# PowerConverters.net
KiCad netlist of a schematic drawn in Altium Designer
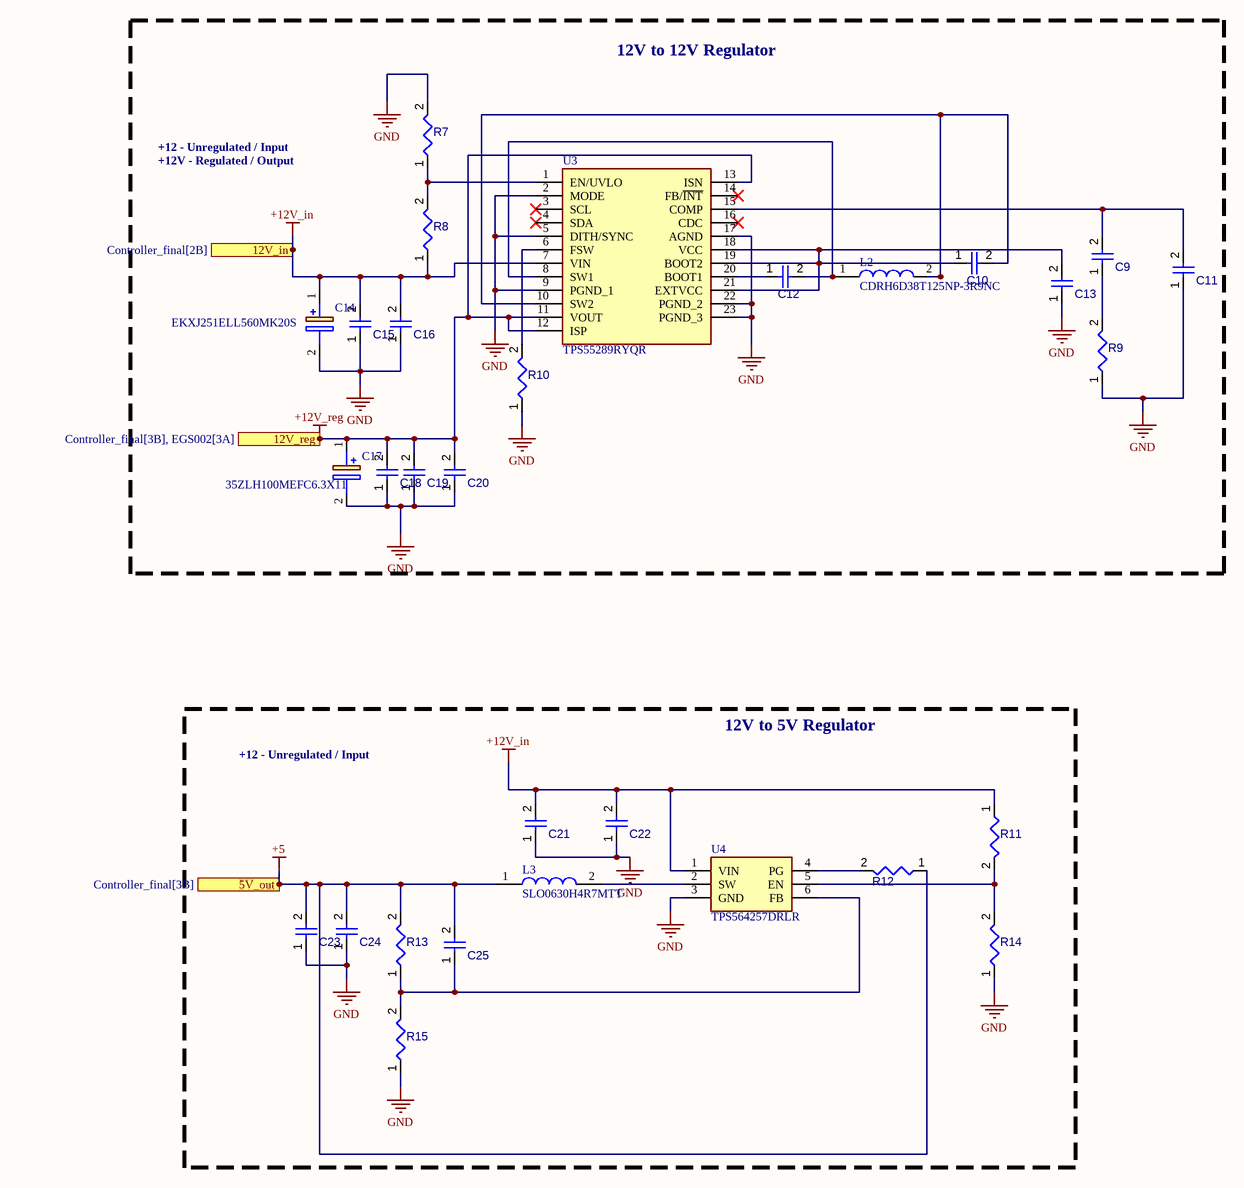
[diagram p0: PowerConverters.SchDoc]

(export (version "E")
  (design (tool "Eeschema 10.0.6"))
  (components
    (comp (ref "C9")
      (value "Capacitor 1nF +/-20% 50V 0402")
      (footprint "CAPC0402(1005)33_L")
      (description "Chip Capacitor, 1nF +/-20%, 50V, 0402, Thickness 0.33 mm")
      (fields (field (name "TOLERANCE") "10%"))
      (libsource (lib "Rahulb 23") (part "CAP-NP-2"))
    )
    (comp (ref "C10")
      (value "Capacitor 100 nF +/-10% 50 V 0603")
      (footprint "CAPC1608X90X40NL10T20")
      (description "Chip Capacitor, 100 nF, +/- 10%, 50 V, 0603 (1608 Metric)")
      (fields (field (name "TOLERANCE") "10%"))
      (libsource (lib "Rahulb 23") (part "CAP-NP-2"))
    )
    (comp (ref "C11")
      (value "Capacitor 1 uF +/- 10% 25 V 0805")
      (footprint "CAPC2013X145X50ML20T25")
      (description "Chip Capacitor, 5.1pF, +/-10%, 250 V, 0805 (2012 Metric)")
      (fields (field (name "TOLERANCE") "10%"))
      (libsource (lib "Rahulb 23") (part "CAP-NP-2"))
    )
    (comp (ref "C12")
      (value "Capacitor 100 nF +/-10% 50 V 0603")
      (footprint "CAPC1608X90X40NL10T20")
      (description "Chip Capacitor, 100 nF, +/- 10%, 50 V, 0603 (1608 Metric)")
      (fields (field (name "TOLERANCE") "10%"))
      (libsource (lib "Rahulb 23") (part "CAP-NP-2"))
    )
    (comp (ref "C13")
      (value "Capacitor 4.7µF +/-40% 25V 0805")
      (footprint "CAPC0805(2012)145_L")
      (description "Chip Capacitor, 4.7µF +/-40%, 25V, 0805, Thickness 1.45 mm")
      (fields (field (name "TOLERANCE") "20%"))
      (libsource (lib "Rahulb 23") (part "CAP-NP-2"))
    )
    (comp (ref "C14")
      (value "EKXJ251ELL560MK20S")
      (footprint "CAPPRD500W60D1275H2000 - duplicate")
      (description "56uF 250V Aluminum Electrolytic Capacitors Through Hole,D12.5xL20mm 10000hrs@105℃")
      (fields
        (field (name "MANUFACTURER_PART_NUMBER") "UPW0J222MHD")
        (field (name "MOUSER PART NUMBER") "647-UPW0J222MHD")
      )
      (libsource (lib "myComponents") (part "UPW0J222MHD"))
    )
    (comp (ref "C15")
      (value "Capacitor 22µF +/-40% 16V 0805")
      (footprint "CAPC0805(2012)145_L")
      (description "Chip Capacitor, 22µF +/-20%, 25V, 0805, Thickness 1.45 mm X5R")
      (fields (field (name "TOLERANCE") "5%"))
      (libsource (lib "Rahulb 23") (part "CAP-NP-2"))
    )
    (comp (ref "C16")
      (value "Capacitor 1µF +/-40% 50V 0603")
      (footprint "CAPC0603(1608)100_L")
      (description "Chip Capacitor, 1µF +/-40%, 50V, 0603, Thickness 1 mm")
      (fields (field (name "TOLERANCE") "10%"))
      (libsource (lib "Rahulb 23") (part "CAP-NP-2"))
    )
    (comp (ref "C17")
      (value "35ZLH100MEFC6.3X11")
      (footprint "CAPPRD250W50D680H1250")
      (description "100uF 35V Aluminum Electrolytic Capacitors Through Hole,D6.3xL11mm 6000hrs@105℃")
      (fields
        (field (name "MANUFACTURER_PART_NUMBER") "MAL203856101E3")
        (field (name "MOUSER PART NUMBER") "594-MAL203856101E3")
      )
      (libsource (lib "myComponents") (part "MAL203856101E3"))
    )
    (comp (ref "C18")
      (value "Capacitor 22µF +/-40% 16V 0805")
      (footprint "CAPC0805(2012)145_L")
      (description "Chip Capacitor, 22µF +/-20%, 25V, 0805, Thickness 1.45 mm X5R")
      (fields (field (name "TOLERANCE") "5%"))
      (libsource (lib "Rahulb 23") (part "CAP-NP-2"))
    )
    (comp (ref "C19")
      (value "Capacitor 22µF +/-40% 16V 0805")
      (footprint "CAPC0805(2012)145_L")
      (description "Chip Capacitor, 22µF +/-20%, 25V, 0805, Thickness 1.45 mm X5R")
      (fields (field (name "TOLERANCE") "5%"))
      (libsource (lib "Rahulb 23") (part "CAP-NP-2"))
    )
    (comp (ref "C20")
      (value "Capacitor 1µF +/-40% 50V 0603")
      (footprint "CAPC0603(1608)100_L")
      (description "Chip Capacitor, 1µF +/-40%, 50V, 0603, Thickness 1 mm")
      (fields (field (name "TOLERANCE") "10%"))
      (libsource (lib "Rahulb 23") (part "CAP-NP-2"))
    )
    (comp (ref "C21")
      (value "Capacitor 22µF +/-40% 16V 0805")
      (footprint "CAPC0805(2012)145_L")
      (description "Chip Capacitor, 22µF +/-20%, 25V, 0805, Thickness 1.45 mm X5R")
      (fields (field (name "TOLERANCE") "5%"))
      (libsource (lib "Rahulb 23") (part "CAP-NP-2"))
    )
    (comp (ref "C22")
      (value "Capacitor 100 nF +/-10% 50 V 0603")
      (footprint "CAPC1608X90X40NL10T20")
      (description "Chip Capacitor, 100 nF, +/- 10%, 50 V, 0603 (1608 Metric)")
      (fields (field (name "TOLERANCE") "10%"))
      (libsource (lib "Rahulb 23") (part "CAP-NP-2"))
    )
    (comp (ref "C23")
      (value "Capacitor 22µF +/-40% 16V 0805")
      (footprint "CAPC0805(2012)145_L")
      (description "Chip Capacitor, 22µF +/-20%, 25V, 0805, Thickness 1.45 mm X5R")
      (fields (field (name "TOLERANCE") "5%"))
      (libsource (lib "Rahulb 23") (part "CAP-NP-2"))
    )
    (comp (ref "C24")
      (value "Capacitor 100 nF +/-10% 50 V 0603")
      (footprint "CAPC1608X90X40NL10T20")
      (description "Chip Capacitor, 100 nF, +/- 10%, 50 V, 0603 (1608 Metric)")
      (fields (field (name "TOLERANCE") "10%"))
      (libsource (lib "Rahulb 23") (part "CAP-NP-2"))
    )
    (comp (ref "C25")
      (value "Capacitor 10 pF +/- 0.25 pF 50 V 0603")
      (footprint "CAPC1608X87X35NL15T15")
      (description "Chip Capacitor, 10 pF, +/- 0.25 pF, 50 V, 0603 (1608 Metric)")
      (fields (field (name "TOLERANCE") "0.25%"))
      (libsource (lib "Rahulb 23") (part "CAP-NP-2"))
    )
    (comp (ref "L2")
      (value "CDRH6D38T125NP-3R9NC")
      (footprint "SamacSys:CDRH6D18HPNP101PC")
      (description "Inductor 3.9uH ,19.6mOhm, SMD, 6.7mm X 6.7mm")
      (fields (field (name "MANUFACTURER_PART_NUMBER") "CDRH6D18HPNP-101PC"))
      (libsource (lib "*") (part "CDRH6D18HPNP-101PC"))
    )
    (comp (ref "L3")
      (value "SLO0630H4R7MTT")
      (footprint "INDPM7166X300N")
      (description "5.5A 4.7uH ±20% 9A 38mΩ Magnetic Shielded Inductor SMD,7.1x6.6mm Fixed Inductors RoHS")
      (fields
        (field (name "MANUFACTURER_PART_NUMBER") "SRP6530A-R47M")
        (field (name "MOUSER PART NUMBER") "652-SRP6530A-R47M")
      )
      (libsource (lib "myComponents") (part "SRP6530A-R47M"))
    )
    (comp (ref "R7")
      (value "Resistor 100k +/-1% 1206 250 mW")
      (footprint "RESC3216X60X45ML15T20")
      (description "Chip Resistor, 100 KOhm, +/- 1%, 0.25 W, -55 to 155 degC, 1206 (3216 Metric)")
      (fields (field (name "TOLERANCE") "1%") (field (name "POWER") "250mW"))
      (libsource (lib "Rahulb 23") (part "RES-2"))
    )
    (comp (ref "R8")
      (value "Resistor 100k +/-1% 0603 100 mW")
      (footprint "RESC1608X55X25ML10T15")
      (description "Chip Resistor, 715 KOhm, +/- 1%, 0.1 W, -55 to 155 degC, 0603 (1608 Metric)")
      (fields (field (name "TOLERANCE") "1%") (field (name "POWER") "100mW"))
      (libsource (lib "Rahulb 23") (part "RES-2"))
    )
    (comp (ref "R9")
      (value "Resistor 100k +/-1% 0603 100 mW")
      (footprint "RESC1608X55X25ML10T15")
      (description "Chip Resistor, 105 KOhm, +/- 1%, 0.1 W, -55 to 155 degC, 0603 (1608 Metric)")
      (fields (field (name "TOLERANCE") "1%") (field (name "POWER") "100mW"))
      (libsource (lib "Rahulb 23") (part "RES-2"))
    )
    (comp (ref "R10")
      (value "Resistor 100k +/-1% 1206 250 mW")
      (footprint "RESC3216X60X45ML15T20")
      (description "Chip Resistor, 48.7 KOhm, +/- 1%, 0.25 W, -55 to 155 degC, 200V, 1206 (3216 Metric)")
      (fields (field (name "TOLERANCE") "1%") (field (name "POWER") "250mW"))
      (libsource (lib "Rahulb 23") (part "RES-2"))
    )
    (comp (ref "R11")
      (value "210 kOhms 0805")
      (footprint "RESC0805(2012)_L")
      (description "210kΩ ±1% 125mW 0805 Thick Film Resistor")
      (fields (field (name "TOLERANCE") "5%") (field (name "POWER") "125mW"))
      (libsource (lib "Rahulb 23") (part "1KR5J"))
    )
    (comp (ref "R12")
      (value "Resistor 10k +/-1% 0805 125 mW")
      (footprint "RESC2013X50X35ML15T15")
      (description "Chip Resistor, 10 KOhm, +/- 1%, 125 mW, -55 to 155 degC, 0805 (2012 Metric)")
      (fields (field (name "TOLERANCE") "1%") (field (name "POWER") "125mW"))
      (libsource (lib "Rahulb 23") (part "RES-2"))
    )
    (comp (ref "R13")
      (value "Resistor 125mW 220kΩ 0805")
      (footprint "RESC2013X70X40ML20T20")
      (description "125mW 220kΩ 150V Thick Film Resistor ±100ppm/℃ ±1% 0805 Chip Resistor - Surface Mount RoHS")
      (fields (field (name "TOLERANCE") "1%") (field (name "POWER") "125mW"))
      (libsource (lib "Rahulb 23") (part "RES-2"))
    )
    (comp (ref "R14")
      (value "Resistor 30k +/-1% 0805 125 mW")
      (footprint "RESC2013X50X35ML15T15")
      (description "30kΩ ±1% 125mW 0805 Thick Film Resistor")
      (fields (field (name "TOLERANCE") "1%") (field (name "POWER") "125mW"))
      (libsource (lib "Rahulb 23") (part "RES-2"))
    )
    (comp (ref "R15")
      (value "Resistor 30k +/-1% 0805 125 mW")
      (footprint "RESC2013X50X35ML15T15")
      (description "30kΩ ±1% 125mW 0805 Thick Film Resistor")
      (fields (field (name "TOLERANCE") "1%") (field (name "POWER") "125mW"))
      (libsource (lib "Rahulb 23") (part "RES-2"))
    )
    (comp (ref "U3")
      (value "TPS55289RYQR")
      (footprint "TPS55289RYQR")
      (description "Integrated Circuit")
      (fields (field (name "MOUSER PART NUMBER") "595-TPS55289RYQR"))
      (libsource (lib "myComponents") (part "TPS55289RYQR"))
    )
    (comp (ref "U4")
      (value "TPS564257DRLR")
      (footprint "SOTFL50P160X60-6N")
      (description "Integrated Circuit")
      (fields (field (name "MOUSER PART NUMBER") "595-TPS564257DRLR"))
      (libsource (lib "myComponents") (part "TPS564257DRLR"))
    )
  )
  (nets
    (net (code "1") (name "+5") (class "Default")
      (node (ref "C23") (pin "2") (pinfunction "2_2") (pintype "passive"))
      (node (ref "C24") (pin "2") (pinfunction "2_2") (pintype "passive"))
      (node (ref "C25") (pin "2") (pinfunction "2_2") (pintype "passive"))
      (node (ref "L3") (pin "1") (pinfunction "1_1") (pintype "passive"))
      (node (ref "R12") (pin "1") (pinfunction "1_1") (pintype "passive"))
      (node (ref "R13") (pin "2") (pinfunction "2_2") (pintype "passive"))
    )
    (net (code "2") (name "+12V_in") (class "Default")
      (node (ref "C14") (pin "1") (pinfunction "+_1") (pintype "passive"))
      (node (ref "C15") (pin "2") (pinfunction "2_2") (pintype "passive"))
      (node (ref "C16") (pin "2") (pinfunction "2_2") (pintype "passive"))
      (node (ref "C21") (pin "2") (pinfunction "2_2") (pintype "passive"))
      (node (ref "C22") (pin "2") (pinfunction "2_2") (pintype "passive"))
      (node (ref "R11") (pin "1") (pinfunction "1_1") (pintype "passive"))
      (node (ref "R8") (pin "1") (pinfunction "1_1") (pintype "passive"))
      (node (ref "U3") (pin "7") (pinfunction "VIN_7") (pintype "passive"))
      (node (ref "U4") (pin "1") (pinfunction "VIN_1") (pintype "passive"))
    )
    (net (code "3") (name "+12V_reg") (class "Default")
      (node (ref "C17") (pin "1") (pinfunction "+_1") (pintype "passive"))
      (node (ref "C18") (pin "2") (pinfunction "2_2") (pintype "passive"))
      (node (ref "C19") (pin "2") (pinfunction "2_2") (pintype "passive"))
      (node (ref "C20") (pin "2") (pinfunction "2_2") (pintype "passive"))
      (node (ref "U3") (pin "11") (pinfunction "VOUT_11") (pintype "passive"))
      (node (ref "U3") (pin "12") (pinfunction "ISP_12") (pintype "passive"))
      (node (ref "U3") (pin "13") (pinfunction "ISN_13") (pintype "passive"))
    )
    (net (code "4") (name "GND") (class "Default")
      (node (ref "C11") (pin "1") (pinfunction "1_1") (pintype "passive"))
      (node (ref "C13") (pin "1") (pinfunction "1_1") (pintype "passive"))
      (node (ref "C14") (pin "2") (pinfunction "-_2") (pintype "passive"))
      (node (ref "C15") (pin "1") (pinfunction "1_1") (pintype "passive"))
      (node (ref "C16") (pin "1") (pinfunction "1_1") (pintype "passive"))
      (node (ref "C17") (pin "2") (pinfunction "-_2") (pintype "passive"))
      (node (ref "C18") (pin "1") (pinfunction "1_1") (pintype "passive"))
      (node (ref "C19") (pin "1") (pinfunction "1_1") (pintype "passive"))
      (node (ref "C20") (pin "1") (pinfunction "1_1") (pintype "passive"))
      (node (ref "C21") (pin "1") (pinfunction "1_1") (pintype "passive"))
      (node (ref "C22") (pin "1") (pinfunction "1_1") (pintype "passive"))
      (node (ref "C23") (pin "1") (pinfunction "1_1") (pintype "passive"))
      (node (ref "C24") (pin "1") (pinfunction "1_1") (pintype "passive"))
      (node (ref "R10") (pin "1") (pinfunction "1_1") (pintype "passive"))
      (node (ref "R14") (pin "1") (pinfunction "1_1") (pintype "passive"))
      (node (ref "R15") (pin "1") (pinfunction "1_1") (pintype "passive"))
      (node (ref "R7") (pin "2") (pinfunction "2_2") (pintype "passive"))
      (node (ref "R9") (pin "1") (pinfunction "1_1") (pintype "passive"))
      (node (ref "U3") (pin "17") (pinfunction "AGND_17") (pintype "passive"))
      (node (ref "U3") (pin "2") (pinfunction "MODE_2") (pintype "passive"))
      (node (ref "U3") (pin "22") (pinfunction "PGND_2_22") (pintype "passive"))
      (node (ref "U3") (pin "23") (pinfunction "PGND_3_23") (pintype "passive"))
      (node (ref "U3") (pin "5") (pinfunction "DITH/SYNC_5") (pintype "passive"))
      (node (ref "U3") (pin "9") (pinfunction "PGND_1_9") (pintype "passive"))
      (node (ref "U4") (pin "3") (pinfunction "GND_3") (pintype "passive"))
    )
    (net (code "5") (name "Net-(C9-Pad1)") (class "Default")
      (node (ref "C9") (pin "1") (pinfunction "1_1") (pintype "passive"))
      (node (ref "R9") (pin "2") (pinfunction "2_2") (pintype "passive"))
    )
    (net (code "6") (name "Net-(U3-BOOT1)") (class "Default")
      (node (ref "C12") (pin "1") (pinfunction "1_1") (pintype "passive"))
      (node (ref "U3") (pin "20") (pinfunction "BOOT1_20") (pintype "passive"))
    )
    (net (code "7") (name "Net-(U3-BOOT2)") (class "Default")
      (node (ref "C10") (pin "1") (pinfunction "1_1") (pintype "passive"))
      (node (ref "C13") (pin "2") (pinfunction "2_2") (pintype "passive"))
      (node (ref "U3") (pin "18") (pinfunction "VCC_18") (pintype "passive"))
      (node (ref "U3") (pin "19") (pinfunction "BOOT2_19") (pintype "passive"))
      (node (ref "U3") (pin "21") (pinfunction "EXTVCC_21") (pintype "passive"))
    )
    (net (code "8") (name "Net-(U3-COMP)") (class "Default")
      (node (ref "C11") (pin "2") (pinfunction "2_2") (pintype "passive"))
      (node (ref "C9") (pin "2") (pinfunction "2_2") (pintype "passive"))
      (node (ref "U3") (pin "15") (pinfunction "COMP_15") (pintype "passive"))
    )
    (net (code "9") (name "Net-(U3-EN{slash}UVLO)") (class "Default")
      (node (ref "R7") (pin "1") (pinfunction "1_1") (pintype "passive"))
      (node (ref "R8") (pin "2") (pinfunction "2_2") (pintype "passive"))
      (node (ref "U3") (pin "1") (pinfunction "EN/UVLO_1") (pintype "passive"))
    )
    (net (code "10") (name "Net-(U3-FSW)") (class "Default")
      (node (ref "R10") (pin "2") (pinfunction "2_2") (pintype "passive"))
      (node (ref "U3") (pin "6") (pinfunction "FSW_6") (pintype "passive"))
    )
    (net (code "11") (name "Net-(U3-SW1)") (class "Default")
      (node (ref "C12") (pin "2") (pinfunction "2_2") (pintype "passive"))
      (node (ref "L2") (pin "1") (pinfunction "1_1") (pintype "passive"))
      (node (ref "U3") (pin "8") (pinfunction "SW1_8") (pintype "passive"))
    )
    (net (code "12") (name "Net-(U3-SW2)") (class "Default")
      (node (ref "C10") (pin "2") (pinfunction "2_2") (pintype "passive"))
      (node (ref "L2") (pin "2") (pinfunction "2_2") (pintype "passive"))
      (node (ref "U3") (pin "10") (pinfunction "SW2_10") (pintype "passive"))
    )
    (net (code "13") (name "Net-(U4-EN)") (class "Default")
      (node (ref "R11") (pin "2") (pinfunction "2_2") (pintype "passive"))
      (node (ref "R14") (pin "2") (pinfunction "2_2") (pintype "passive"))
      (node (ref "U4") (pin "5") (pinfunction "EN_5") (pintype "passive"))
    )
    (net (code "14") (name "Net-(U4-FB)") (class "Default")
      (node (ref "C25") (pin "1") (pinfunction "1_1") (pintype "passive"))
      (node (ref "R13") (pin "1") (pinfunction "1_1") (pintype "passive"))
      (node (ref "R15") (pin "2") (pinfunction "2_2") (pintype "passive"))
      (node (ref "U4") (pin "6") (pinfunction "FB_6") (pintype "passive"))
    )
    (net (code "15") (name "Net-(U4-PG)") (class "Default")
      (node (ref "R12") (pin "2") (pinfunction "2_2") (pintype "passive"))
      (node (ref "U4") (pin "4") (pinfunction "PG_4") (pintype "passive"))
    )
    (net (code "16") (name "Net-(U4-SW)") (class "Default")
      (node (ref "L3") (pin "2") (pinfunction "2_2") (pintype "passive"))
      (node (ref "U4") (pin "2") (pinfunction "SW_2") (pintype "passive"))
    )
    (net (code "17") (name "unconnected-(U3-CDC-Pad16)") (class "Default")
      (node (ref "U3") (pin "16") (pinfunction "CDC_16") (pintype "passive+no_connect"))
    )
    (net (code "18") (name "unconnected-(U3-FB{slash}~{INT}-Pad14)") (class "Default")
      (node (ref "U3") (pin "14") (pinfunction "FB/~{INT}_14") (pintype "passive+no_connect"))
    )
    (net (code "19") (name "unconnected-(U3-SCL-Pad3)") (class "Default")
      (node (ref "U3") (pin "3") (pinfunction "SCL_3") (pintype "passive+no_connect"))
    )
    (net (code "20") (name "unconnected-(U3-SDA-Pad4)") (class "Default")
      (node (ref "U3") (pin "4") (pinfunction "SDA_4") (pintype "passive+no_connect"))
    )
  )
)
